# SIM908.net
KiCad netlist of a schematic drawn in EAGLE
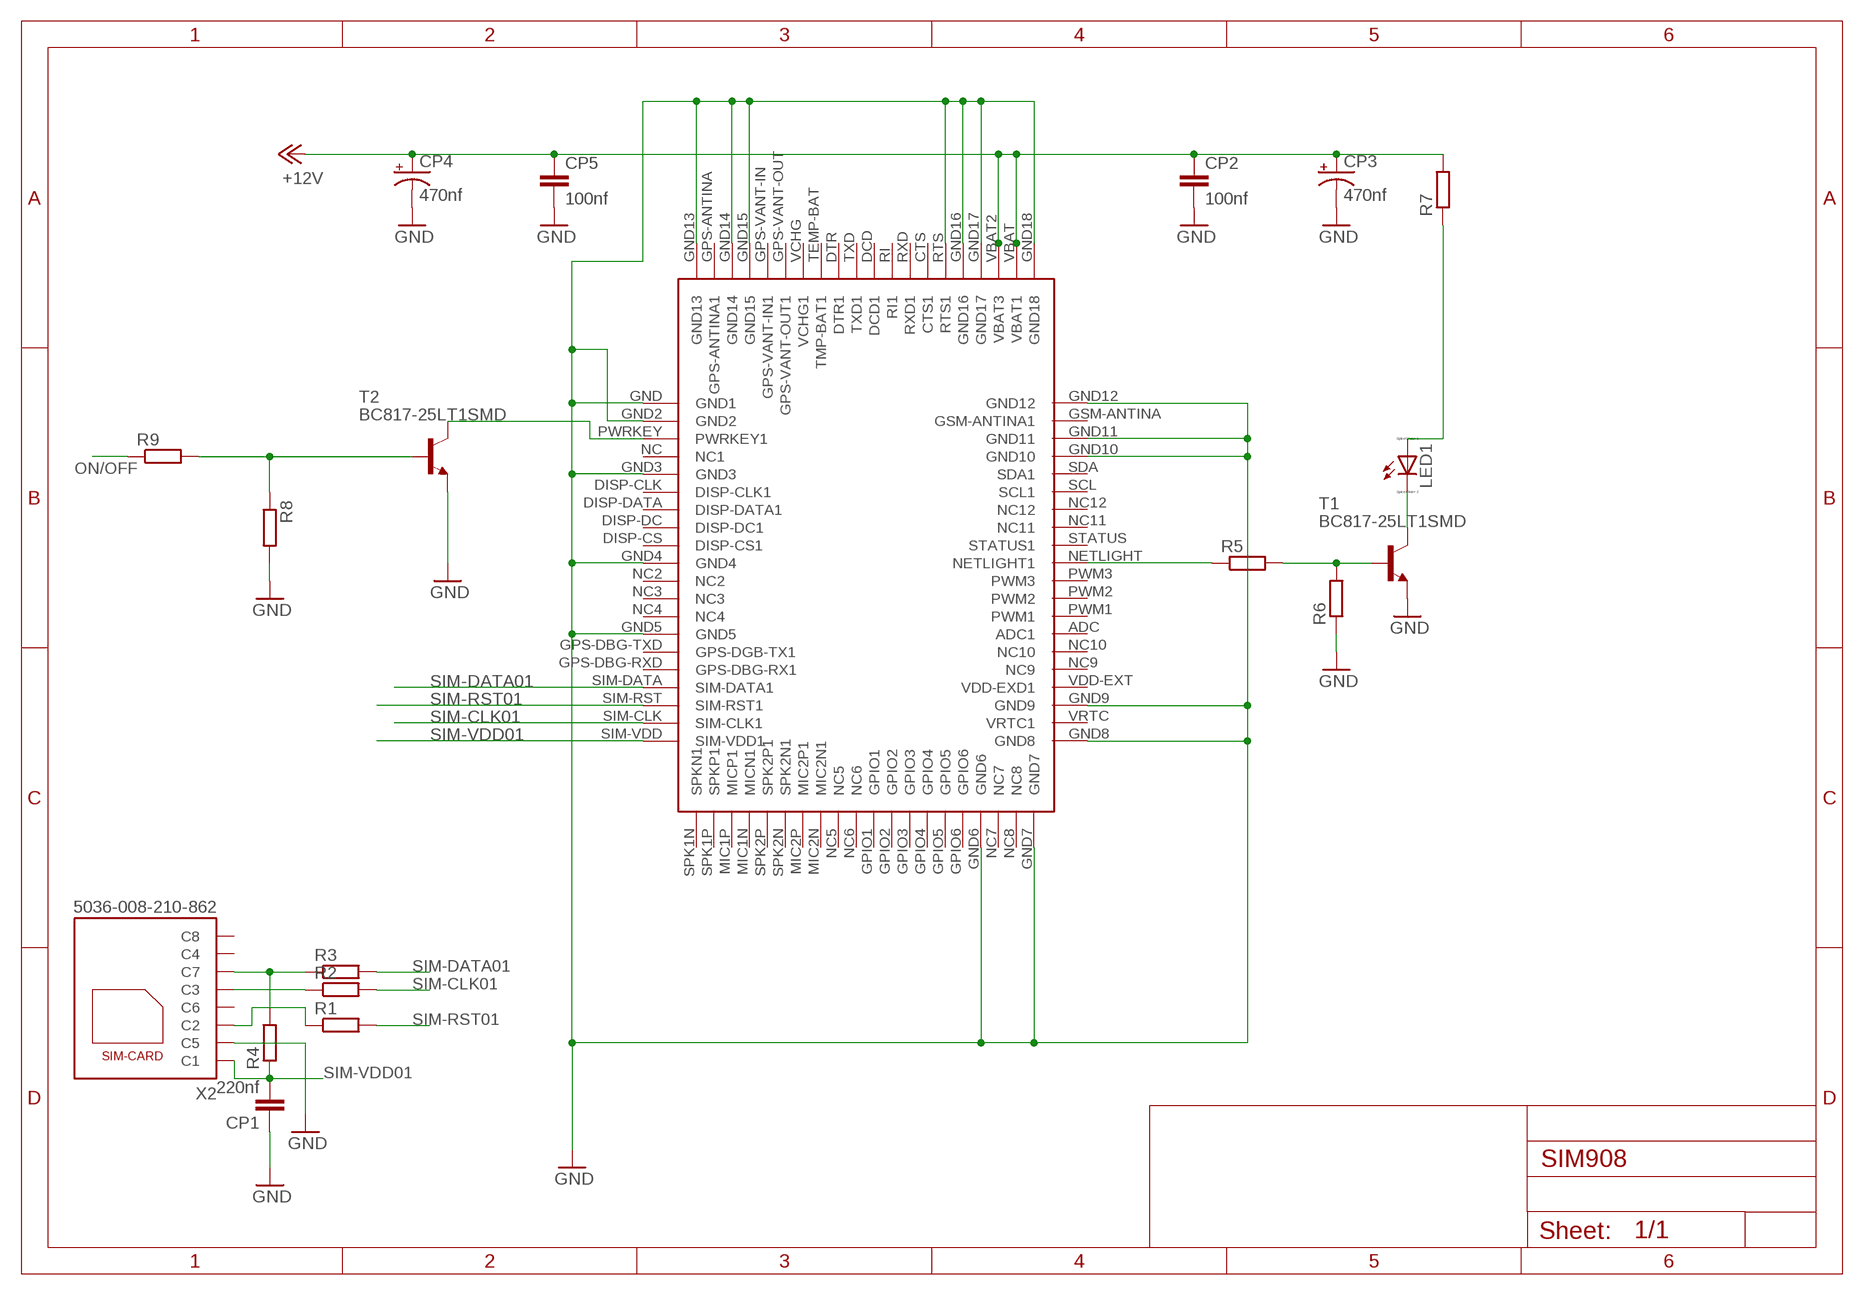
[diagram p0: schematic, sheet 1]

(export (version "E")
  (design (tool "Eeschema 10.0.6"))
  (components
    (comp (ref "CP1")
      (value "220nf")
      (footprint "eagle-import:C15B9")
      (libsource (lib "eagle-import") (part "C15/9"))
    )
    (comp (ref "CP2")
      (value "100nf")
      (footprint "eagle-import:C15B9")
      (libsource (lib "eagle-import") (part "C15/9"))
    )
    (comp (ref "CP3")
      (value "470nf")
      (footprint "eagle-import:153CLV-0807")
      (libsource (lib "eagle-import") (part "CPOL-US153CLV-0807"))
    )
    (comp (ref "CP4")
      (value "470nf")
      (footprint "eagle-import:153CLV-0807")
      (libsource (lib "eagle-import") (part "CPOL-US153CLV-0807"))
    )
    (comp (ref "CP5")
      (value "100nf")
      (footprint "eagle-import:C15B9")
      (libsource (lib "eagle-import") (part "C15/9"))
    )
    (comp (ref "LED1")
      (value "LED_E")
      (footprint "eagle-import:LED_1206")
      (libsource (lib "eagle-import") (part "LED_E"))
    )
    (comp (ref "R1")
      (value "R-EU_0207/12")
      (footprint "eagle-import:0207_12")
      (libsource (lib "eagle-import") (part "R-EU_0207/12"))
    )
    (comp (ref "R2")
      (value "R-EU_0207/12")
      (footprint "eagle-import:0207_12")
      (libsource (lib "eagle-import") (part "R-EU_0207/12"))
    )
    (comp (ref "R3")
      (value "R-EU_0207/12")
      (footprint "eagle-import:0207_12")
      (libsource (lib "eagle-import") (part "R-EU_0207/12"))
    )
    (comp (ref "R4")
      (value "R-EU_0207/12")
      (footprint "eagle-import:0207_12")
      (libsource (lib "eagle-import") (part "R-EU_0207/12"))
    )
    (comp (ref "R5")
      (value "R-EU_0207/12")
      (footprint "eagle-import:0207_12")
      (libsource (lib "eagle-import") (part "R-EU_0207/12"))
    )
    (comp (ref "R6")
      (value "R-EU_0207/12")
      (footprint "eagle-import:0207_12")
      (libsource (lib "eagle-import") (part "R-EU_0207/12"))
    )
    (comp (ref "R7")
      (value "R-EU_0207/12")
      (footprint "eagle-import:0207_12")
      (libsource (lib "eagle-import") (part "R-EU_0207/12"))
    )
    (comp (ref "R8")
      (value "R-EU_0207/12")
      (footprint "eagle-import:0207_12")
      (libsource (lib "eagle-import") (part "R-EU_0207/12"))
    )
    (comp (ref "R9")
      (value "R-EU_0207/12")
      (footprint "eagle-import:0207_12")
      (libsource (lib "eagle-import") (part "R-EU_0207/12"))
    )
    (comp (ref "T1")
      (value "BC817-25LT1SMD")
      (footprint "eagle-import:SOT23-BEC")
      (libsource (lib "eagle-import") (part "BC817SMD-25LT1"))
    )
    (comp (ref "T2")
      (value "BC817-25LT1SMD")
      (footprint "eagle-import:SOT23-BEC")
      (libsource (lib "eagle-import") (part "BC817SMD-25LT1"))
    )
    (comp (ref "U$2")
      (value "SIM908")
      (footprint "eagle-import:SIM908")
      (libsource (lib "eagle-import") (part "SIM908"))
    )
    (comp (ref "X2")
      (value "5036-008-210-862")
      (footprint "eagle-import:5036_008_210_862")
      (libsource (lib "eagle-import") (part "5036-008-210-862"))
    )
  )
  (nets
    (net (code "1") (name "+12V") (class "Default")
      (node (ref "CP2") (pin "1") (pinfunction "1_1") (pintype "passive"))
      (node (ref "CP3") (pin "+") (pinfunction "+_+") (pintype "passive"))
      (node (ref "CP4") (pin "+") (pinfunction "+_+") (pintype "passive"))
      (node (ref "CP5") (pin "1") (pinfunction "1_1") (pintype "passive"))
      (node (ref "R7") (pin "2") (pinfunction "2_2") (pintype "passive"))
      (node (ref "U$2") (pin "VBAT") (pinfunction "VBAT1_VBAT") (pintype "bidirectional"))
      (node (ref "U$2") (pin "VBAT2") (pinfunction "VBAT3_VBAT2") (pintype "bidirectional"))
    )
    (net (code "2") (name "/ON{slash}OFF") (class "Default")
      (node (ref "R9") (pin "1") (pinfunction "1_1") (pintype "passive"))
    )
    (net (code "3") (name "/SIM-CLK01") (class "Default")
      (node (ref "R2") (pin "2") (pinfunction "2_2") (pintype "passive"))
      (node (ref "U$2") (pin "SIM-CLK") (pinfunction "SIM-CLK1_SIM-CLK") (pintype "bidirectional"))
    )
    (net (code "4") (name "/SIM-DATA01") (class "Default")
      (node (ref "R3") (pin "2") (pinfunction "2_2") (pintype "passive"))
      (node (ref "U$2") (pin "SIM-DATA") (pinfunction "SIM-DATA1_SIM-DATA") (pintype "bidirectional"))
    )
    (net (code "5") (name "/SIM-RST01") (class "Default")
      (node (ref "R1") (pin "2") (pinfunction "2_2") (pintype "passive"))
      (node (ref "U$2") (pin "SIM-RST") (pinfunction "SIM-RST1_SIM-RST") (pintype "bidirectional"))
    )
    (net (code "6") (name "/SIM-VDD01") (class "Default")
      (node (ref "CP1") (pin "2") (pinfunction "2_2") (pintype "passive"))
      (node (ref "R4") (pin "1") (pinfunction "1_1") (pintype "passive"))
      (node (ref "U$2") (pin "SIM-VDD") (pinfunction "SIM-VDD1_SIM-VDD") (pintype "bidirectional"))
      (node (ref "X2") (pin "C1") (pinfunction "C1_C1") (pintype "passive"))
    )
    (net (code "7") (name "GND") (class "Default")
      (node (ref "CP1") (pin "1") (pinfunction "1_1") (pintype "passive"))
      (node (ref "CP2") (pin "2") (pinfunction "2_2") (pintype "passive"))
      (node (ref "CP3") (pin "-") (pinfunction "-_-") (pintype "passive"))
      (node (ref "CP4") (pin "-") (pinfunction "-_-") (pintype "passive"))
      (node (ref "CP5") (pin "2") (pinfunction "2_2") (pintype "passive"))
      (node (ref "R6") (pin "1") (pinfunction "1_1") (pintype "passive"))
      (node (ref "R8") (pin "2") (pinfunction "2_2") (pintype "passive"))
      (node (ref "T1") (pin "E") (pinfunction "E_E") (pintype "passive"))
      (node (ref "T2") (pin "E") (pinfunction "E_E") (pintype "passive"))
      (node (ref "U$2") (pin "GND") (pinfunction "GND1_GND") (pintype "bidirectional"))
      (node (ref "U$2") (pin "GND10") (pinfunction "GND10_GND10") (pintype "bidirectional"))
      (node (ref "U$2") (pin "GND11") (pinfunction "GND11_GND11") (pintype "bidirectional"))
      (node (ref "U$2") (pin "GND12") (pinfunction "GND12_GND12") (pintype "bidirectional"))
      (node (ref "U$2") (pin "GND13") (pinfunction "GND13_GND13") (pintype "bidirectional"))
      (node (ref "U$2") (pin "GND14") (pinfunction "GND14_GND14") (pintype "bidirectional"))
      (node (ref "U$2") (pin "GND15") (pinfunction "GND15_GND15") (pintype "bidirectional"))
      (node (ref "U$2") (pin "GND16") (pinfunction "GND16_GND16") (pintype "bidirectional"))
      (node (ref "U$2") (pin "GND17") (pinfunction "GND17_GND17") (pintype "bidirectional"))
      (node (ref "U$2") (pin "GND18") (pinfunction "GND18_GND18") (pintype "bidirectional"))
      (node (ref "U$2") (pin "GND2") (pinfunction "GND2_GND2") (pintype "bidirectional"))
      (node (ref "U$2") (pin "GND3") (pinfunction "GND3_GND3") (pintype "bidirectional"))
      (node (ref "U$2") (pin "GND4") (pinfunction "GND4_GND4") (pintype "bidirectional"))
      (node (ref "U$2") (pin "GND5") (pinfunction "GND5_GND5") (pintype "bidirectional"))
      (node (ref "U$2") (pin "GND6") (pinfunction "GND6_GND6") (pintype "bidirectional"))
      (node (ref "U$2") (pin "GND7") (pinfunction "GND7_GND7") (pintype "bidirectional"))
      (node (ref "U$2") (pin "GND8") (pinfunction "GND8_GND8") (pintype "bidirectional"))
      (node (ref "U$2") (pin "GND9") (pinfunction "GND9_GND9") (pintype "bidirectional"))
      (node (ref "U$2") (pin "RTS") (pinfunction "RTS1_RTS") (pintype "bidirectional"))
      (node (ref "X2") (pin "C5") (pinfunction "C5_C5") (pintype "passive"))
    )
    (net (code "8") (name "Net-(LED1-PadA)") (class "Default")
      (node (ref "LED1") (pin "A") (pinfunction "A_A") (pintype "passive"))
      (node (ref "R7") (pin "1") (pinfunction "1_1") (pintype "passive"))
    )
    (net (code "9") (name "Net-(LED1-PadC)") (class "Default")
      (node (ref "LED1") (pin "C") (pinfunction "C_C") (pintype "passive"))
      (node (ref "T1") (pin "C") (pinfunction "C_C") (pintype "passive"))
    )
    (net (code "10") (name "Net-(R1-Pad1)") (class "Default")
      (node (ref "R1") (pin "1") (pinfunction "1_1") (pintype "passive"))
      (node (ref "X2") (pin "C2") (pinfunction "C2_C2") (pintype "passive"))
    )
    (net (code "11") (name "Net-(R2-Pad1)") (class "Default")
      (node (ref "R2") (pin "1") (pinfunction "1_1") (pintype "passive"))
      (node (ref "X2") (pin "C3") (pinfunction "C3_C3") (pintype "passive"))
    )
    (net (code "12") (name "Net-(R3-Pad1)") (class "Default")
      (node (ref "R3") (pin "1") (pinfunction "1_1") (pintype "passive"))
      (node (ref "R4") (pin "2") (pinfunction "2_2") (pintype "passive"))
      (node (ref "X2") (pin "C7") (pinfunction "C7_C7") (pintype "passive"))
    )
    (net (code "13") (name "Net-(R5-Pad2)") (class "Default")
      (node (ref "R5") (pin "2") (pinfunction "2_2") (pintype "passive"))
      (node (ref "R6") (pin "2") (pinfunction "2_2") (pintype "passive"))
      (node (ref "T1") (pin "B") (pinfunction "B_B") (pintype "passive"))
    )
    (net (code "14") (name "Net-(R8-Pad1)") (class "Default")
      (node (ref "R8") (pin "1") (pinfunction "1_1") (pintype "passive"))
      (node (ref "R9") (pin "2") (pinfunction "2_2") (pintype "passive"))
      (node (ref "T2") (pin "B") (pinfunction "B_B") (pintype "passive"))
    )
    (net (code "15") (name "Net-(U$2-NETLIGHT1)") (class "Default")
      (node (ref "R5") (pin "1") (pinfunction "1_1") (pintype "passive"))
      (node (ref "U$2") (pin "NETLIGHT") (pinfunction "NETLIGHT1_NETLIGHT") (pintype "bidirectional"))
    )
    (net (code "16") (name "Net-(U$2-PWRKEY1)") (class "Default")
      (node (ref "T2") (pin "C") (pinfunction "C_C") (pintype "passive"))
      (node (ref "U$2") (pin "PWRKEY") (pinfunction "PWRKEY1_PWRKEY") (pintype "bidirectional"))
    )
    (net (code "17") (name "unconnected-(U$2-ADC1-PadADC)") (class "Default")
      (node (ref "U$2") (pin "ADC") (pinfunction "ADC1_ADC") (pintype "bidirectional"))
    )
    (net (code "18") (name "unconnected-(U$2-CTS1-PadCTS)") (class "Default")
      (node (ref "U$2") (pin "CTS") (pinfunction "CTS1_CTS") (pintype "bidirectional"))
    )
    (net (code "19") (name "unconnected-(U$2-DCD1-PadDCD)") (class "Default")
      (node (ref "U$2") (pin "DCD") (pinfunction "DCD1_DCD") (pintype "bidirectional"))
    )
    (net (code "20") (name "unconnected-(U$2-DISP-CLK1-PadDISP-CLK)") (class "Default")
      (node (ref "U$2") (pin "DISP-CLK") (pinfunction "DISP-CLK1_DISP-CLK") (pintype "bidirectional"))
    )
    (net (code "21") (name "unconnected-(U$2-DISP-CS1-PadDISP-CS)") (class "Default")
      (node (ref "U$2") (pin "DISP-CS") (pinfunction "DISP-CS1_DISP-CS") (pintype "bidirectional"))
    )
    (net (code "22") (name "unconnected-(U$2-DISP-DATA1-PadDISP-DATA)") (class "Default")
      (node (ref "U$2") (pin "DISP-DATA") (pinfunction "DISP-DATA1_DISP-DATA") (pintype "bidirectional"))
    )
    (net (code "23") (name "unconnected-(U$2-DISP-DC1-PadDISP-DC)") (class "Default")
      (node (ref "U$2") (pin "DISP-DC") (pinfunction "DISP-DC1_DISP-DC") (pintype "bidirectional"))
    )
    (net (code "24") (name "unconnected-(U$2-DTR1-PadDTR)") (class "Default")
      (node (ref "U$2") (pin "DTR") (pinfunction "DTR1_DTR") (pintype "bidirectional"))
    )
    (net (code "25") (name "unconnected-(U$2-GPS-ANTINA1-PadGPS-ANTINA)") (class "Default")
      (node (ref "U$2") (pin "GPS-ANTINA") (pinfunction "GPS-ANTINA1_GPS-ANTINA") (pintype "bidirectional"))
    )
    (net (code "26") (name "unconnected-(U$2-GPS-DBG-RX1-PadGPS-DBG-RXD)") (class "Default")
      (node (ref "U$2") (pin "GPS-DBG-RXD") (pinfunction "GPS-DBG-RX1_GPS-DBG-RXD") (pintype "bidirectional"))
    )
    (net (code "27") (name "unconnected-(U$2-GPS-DGB-TX1-PadGPS-DBG-TXD)") (class "Default")
      (node (ref "U$2") (pin "GPS-DBG-TXD") (pinfunction "GPS-DGB-TX1_GPS-DBG-TXD") (pintype "bidirectional"))
    )
    (net (code "28") (name "unconnected-(U$2-GPS-VANT-IN1-PadGPS-VANT-IN)") (class "Default")
      (node (ref "U$2") (pin "GPS-VANT-IN") (pinfunction "GPS-VANT-IN1_GPS-VANT-IN") (pintype "bidirectional"))
    )
    (net (code "29") (name "unconnected-(U$2-GPS-VANT-OUT1-PadGPS-VANT-OUT)") (class "Default")
      (node (ref "U$2") (pin "GPS-VANT-OUT") (pinfunction "GPS-VANT-OUT1_GPS-VANT-OUT") (pintype "bidirectional"))
    )
    (net (code "30") (name "unconnected-(U$2-GSM-ANTINA1-PadGSM-ANTINA)") (class "Default")
      (node (ref "U$2") (pin "GSM-ANTINA") (pinfunction "GSM-ANTINA1_GSM-ANTINA") (pintype "bidirectional"))
    )
    (net (code "31") (name "unconnected-(U$2-MIC2N1-PadMIC2N)") (class "Default")
      (node (ref "U$2") (pin "MIC2N") (pinfunction "MIC2N1_MIC2N") (pintype "bidirectional"))
    )
    (net (code "32") (name "unconnected-(U$2-MIC2P1-PadMIC2P)") (class "Default")
      (node (ref "U$2") (pin "MIC2P") (pinfunction "MIC2P1_MIC2P") (pintype "bidirectional"))
    )
    (net (code "33") (name "unconnected-(U$2-MICN1-PadMIC1N)") (class "Default")
      (node (ref "U$2") (pin "MIC1N") (pinfunction "MICN1_MIC1N") (pintype "bidirectional"))
    )
    (net (code "34") (name "unconnected-(U$2-MICP1-PadMIC1P)") (class "Default")
      (node (ref "U$2") (pin "MIC1P") (pinfunction "MICP1_MIC1P") (pintype "bidirectional"))
    )
    (net (code "35") (name "unconnected-(U$2-NC1-PadNC)") (class "Default")
      (node (ref "U$2") (pin "NC") (pinfunction "NC1_NC") (pintype "bidirectional"))
    )
    (net (code "36") (name "unconnected-(U$2-PadGPIO1)") (class "Default")
      (node (ref "U$2") (pin "GPIO1") (pinfunction "GPIO1_GPIO1") (pintype "bidirectional"))
    )
    (net (code "37") (name "unconnected-(U$2-PadGPIO2)") (class "Default")
      (node (ref "U$2") (pin "GPIO2") (pinfunction "GPIO2_GPIO2") (pintype "bidirectional"))
    )
    (net (code "38") (name "unconnected-(U$2-PadGPIO3)") (class "Default")
      (node (ref "U$2") (pin "GPIO3") (pinfunction "GPIO3_GPIO3") (pintype "bidirectional"))
    )
    (net (code "39") (name "unconnected-(U$2-PadGPIO4)") (class "Default")
      (node (ref "U$2") (pin "GPIO4") (pinfunction "GPIO4_GPIO4") (pintype "bidirectional"))
    )
    (net (code "40") (name "unconnected-(U$2-PadGPIO5)") (class "Default")
      (node (ref "U$2") (pin "GPIO5") (pinfunction "GPIO5_GPIO5") (pintype "bidirectional"))
    )
    (net (code "41") (name "unconnected-(U$2-PadGPIO6)") (class "Default")
      (node (ref "U$2") (pin "GPIO6") (pinfunction "GPIO6_GPIO6") (pintype "bidirectional"))
    )
    (net (code "42") (name "unconnected-(U$2-PadNC2)") (class "Default")
      (node (ref "U$2") (pin "NC2") (pinfunction "NC2_NC2") (pintype "bidirectional"))
    )
    (net (code "43") (name "unconnected-(U$2-PadNC3)") (class "Default")
      (node (ref "U$2") (pin "NC3") (pinfunction "NC3_NC3") (pintype "bidirectional"))
    )
    (net (code "44") (name "unconnected-(U$2-PadNC4)") (class "Default")
      (node (ref "U$2") (pin "NC4") (pinfunction "NC4_NC4") (pintype "bidirectional"))
    )
    (net (code "45") (name "unconnected-(U$2-PadNC5)") (class "Default")
      (node (ref "U$2") (pin "NC5") (pinfunction "NC5_NC5") (pintype "bidirectional"))
    )
    (net (code "46") (name "unconnected-(U$2-PadNC6)") (class "Default")
      (node (ref "U$2") (pin "NC6") (pinfunction "NC6_NC6") (pintype "bidirectional"))
    )
    (net (code "47") (name "unconnected-(U$2-PadNC7)") (class "Default")
      (node (ref "U$2") (pin "NC7") (pinfunction "NC7_NC7") (pintype "bidirectional"))
    )
    (net (code "48") (name "unconnected-(U$2-PadNC8)") (class "Default")
      (node (ref "U$2") (pin "NC8") (pinfunction "NC8_NC8") (pintype "bidirectional"))
    )
    (net (code "49") (name "unconnected-(U$2-PadNC9)") (class "Default")
      (node (ref "U$2") (pin "NC9") (pinfunction "NC9_NC9") (pintype "bidirectional"))
    )
    (net (code "50") (name "unconnected-(U$2-PadNC10)") (class "Default")
      (node (ref "U$2") (pin "NC10") (pinfunction "NC10_NC10") (pintype "bidirectional"))
    )
    (net (code "51") (name "unconnected-(U$2-PadNC11)") (class "Default")
      (node (ref "U$2") (pin "NC11") (pinfunction "NC11_NC11") (pintype "bidirectional"))
    )
    (net (code "52") (name "unconnected-(U$2-PadNC12)") (class "Default")
      (node (ref "U$2") (pin "NC12") (pinfunction "NC12_NC12") (pintype "bidirectional"))
    )
    (net (code "53") (name "unconnected-(U$2-PadPWM1)") (class "Default")
      (node (ref "U$2") (pin "PWM1") (pinfunction "PWM1_PWM1") (pintype "bidirectional"))
    )
    (net (code "54") (name "unconnected-(U$2-PadPWM2)") (class "Default")
      (node (ref "U$2") (pin "PWM2") (pinfunction "PWM2_PWM2") (pintype "bidirectional"))
    )
    (net (code "55") (name "unconnected-(U$2-PadPWM3)") (class "Default")
      (node (ref "U$2") (pin "PWM3") (pinfunction "PWM3_PWM3") (pintype "bidirectional"))
    )
    (net (code "56") (name "unconnected-(U$2-RI1-PadRI)") (class "Default")
      (node (ref "U$2") (pin "RI") (pinfunction "RI1_RI") (pintype "bidirectional"))
    )
    (net (code "57") (name "unconnected-(U$2-RXD1-PadRXD)") (class "Default")
      (node (ref "U$2") (pin "RXD") (pinfunction "RXD1_RXD") (pintype "bidirectional"))
    )
    (net (code "58") (name "unconnected-(U$2-SCL1-PadSCL)") (class "Default")
      (node (ref "U$2") (pin "SCL") (pinfunction "SCL1_SCL") (pintype "bidirectional"))
    )
    (net (code "59") (name "unconnected-(U$2-SDA1-PadSDA)") (class "Default")
      (node (ref "U$2") (pin "SDA") (pinfunction "SDA1_SDA") (pintype "bidirectional"))
    )
    (net (code "60") (name "unconnected-(U$2-SPK2N1-PadSPK2N)") (class "Default")
      (node (ref "U$2") (pin "SPK2N") (pinfunction "SPK2N1_SPK2N") (pintype "bidirectional"))
    )
    (net (code "61") (name "unconnected-(U$2-SPK2P1-PadSPK2P)") (class "Default")
      (node (ref "U$2") (pin "SPK2P") (pinfunction "SPK2P1_SPK2P") (pintype "bidirectional"))
    )
    (net (code "62") (name "unconnected-(U$2-SPKN1-PadSPK1N)") (class "Default")
      (node (ref "U$2") (pin "SPK1N") (pinfunction "SPKN1_SPK1N") (pintype "bidirectional"))
    )
    (net (code "63") (name "unconnected-(U$2-SPKP1-PadSPK1P)") (class "Default")
      (node (ref "U$2") (pin "SPK1P") (pinfunction "SPKP1_SPK1P") (pintype "bidirectional"))
    )
    (net (code "64") (name "unconnected-(U$2-STATUS1-PadSTATUS)") (class "Default")
      (node (ref "U$2") (pin "STATUS") (pinfunction "STATUS1_STATUS") (pintype "bidirectional"))
    )
    (net (code "65") (name "unconnected-(U$2-TMP-BAT1-PadTEMP-BAT)") (class "Default")
      (node (ref "U$2") (pin "TEMP-BAT") (pinfunction "TMP-BAT1_TEMP-BAT") (pintype "bidirectional"))
    )
    (net (code "66") (name "unconnected-(U$2-TXD1-PadTXD)") (class "Default")
      (node (ref "U$2") (pin "TXD") (pinfunction "TXD1_TXD") (pintype "bidirectional"))
    )
    (net (code "67") (name "unconnected-(U$2-VCHG1-PadVCHG)") (class "Default")
      (node (ref "U$2") (pin "VCHG") (pinfunction "VCHG1_VCHG") (pintype "bidirectional"))
    )
    (net (code "68") (name "unconnected-(U$2-VDD-EXD1-PadVDD-EXT)") (class "Default")
      (node (ref "U$2") (pin "VDD-EXT") (pinfunction "VDD-EXD1_VDD-EXT") (pintype "bidirectional"))
    )
    (net (code "69") (name "unconnected-(U$2-VRTC1-PadVRTC)") (class "Default")
      (node (ref "U$2") (pin "VRTC") (pinfunction "VRTC1_VRTC") (pintype "bidirectional"))
    )
    (net (code "70") (name "unconnected-(X2-PadC4)") (class "Default")
      (node (ref "X2") (pin "C4") (pinfunction "C4_C4") (pintype "passive"))
    )
    (net (code "71") (name "unconnected-(X2-PadC6)") (class "Default")
      (node (ref "X2") (pin "C6") (pinfunction "C6_C6") (pintype "passive"))
    )
    (net (code "72") (name "unconnected-(X2-PadC8)") (class "Default")
      (node (ref "X2") (pin "C8") (pinfunction "C8_C8") (pintype "passive"))
    )
  )
)
